# MCU_MKE185F512VLH16.net
KiCad netlist of a schematic drawn in Altium Designer
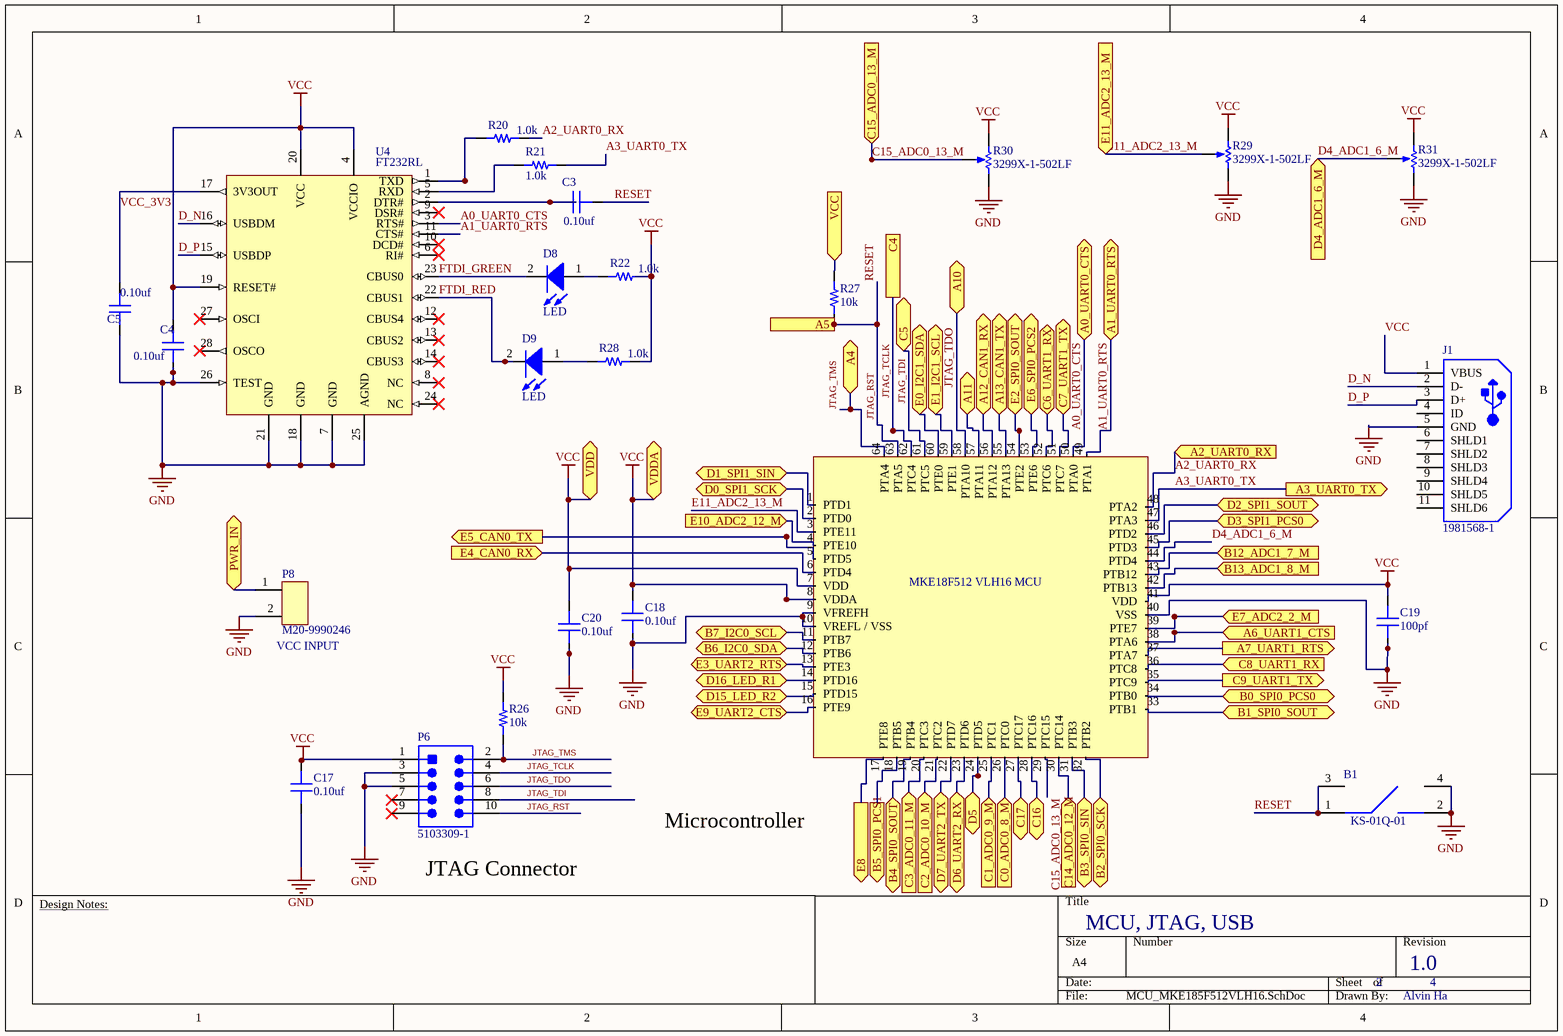
[diagram p0: MCU_MKE185F512VLH16.SchDoc]

(export (version "E")
  (design (tool "Eeschema 10.0.6"))
  (components
    (comp (ref "B1")
      (value "KS-01Q-01")
      (footprint "KS-01Q-01")
      (description "RESET button")
      (fields (field (name "CREATED_BY") "Austin") (field (name "UPDATED_BY") "Null"))
      (libsource (lib "Altium-Lib") (part "KS-01Q-01"))
    )
    (comp (ref "C3")
      (value "0.10uf")
      (footprint "CAP 0603/1608")
      (fields
        (field (name "Comment") "Capacitor MLCC 0.10uf 25V CAP 0603/1608")
        (field (name "CREATED_BY") "Nick Mah")
      )
      (libsource (lib "Altium-Lib") (part "Capacitor"))
    )
    (comp (ref "C4")
      (value "0.10uf")
      (footprint "CAP 0603/1608")
      (fields
        (field (name "Comment") "Capacitor MLCC 0.10uf 25V CAP 0603/1608")
        (field (name "CREATED_BY") "Nick Mah")
      )
      (libsource (lib "Altium-Lib") (part "Capacitor"))
    )
    (comp (ref "C5")
      (value "0.10uf")
      (footprint "CAP 0603/1608")
      (fields
        (field (name "Comment") "Capacitor MLCC 0.10uf 25V CAP 0603/1608")
        (field (name "CREATED_BY") "Nick Mah")
      )
      (libsource (lib "Altium-Lib") (part "Capacitor"))
    )
    (comp (ref "C17")
      (value "0.10uf")
      (footprint "CAP 0603/1608")
      (fields
        (field (name "Comment") "Capacitor MLCC 0.10uf 16V CAP 0603/1608")
        (field (name "CREATED_BY") "Nick Mah")
      )
      (libsource (lib "Altium-Lib") (part "Capacitor"))
    )
    (comp (ref "C18")
      (value "0.10uf")
      (footprint "CAP 0603/1608")
      (fields
        (field (name "Comment") "Capacitor MLCC 0.10uf 25V CAP 0603/1608")
        (field (name "CREATED_BY") "Nick Mah")
      )
      (libsource (lib "Altium-Lib") (part "Capacitor"))
    )
    (comp (ref "C19")
      (value "100pf")
      (footprint "CAP 0603/1608")
      (fields
        (field (name "Comment") "Capacitor MLCC 100pf 25V CAP 0603/1608")
        (field (name "CREATED_BY") "Nick Mah")
      )
      (libsource (lib "Altium-Lib") (part "Capacitor"))
    )
    (comp (ref "C20")
      (value "0.10uf")
      (footprint "CAP 0603/1608")
      (fields
        (field (name "Comment") "Capacitor MLCC 0.10uf 25V CAP 0603/1608")
        (field (name "CREATED_BY") "Nick Mah")
      )
      (libsource (lib "Altium-Lib") (part "Capacitor"))
    )
    (comp (ref "D8") (value "LED") (footprint "0805_LED") (libsource (lib "Altium-Lib") (part "LED")))
    (comp (ref "D9") (value "LED") (footprint "0805_LED") (libsource (lib "Altium-Lib") (part "LED")))
    (comp (ref "J1")
      (value "1981568-1")
      (footprint "TECO-1981568-5_V")
      (description "USB Micro Type B")
      (fields (field (name "CREATED_BY") "Aiku"))
      (libsource (lib "Altium-Lib") (part "USB-5-6SHLD"))
    )
    (comp (ref "P6")
      (value "5103309-1")
      (footprint "HDR2X5_SMT")
      (description "2 row connector")
      (fields (field (name "CREATED_BY") "Aiku"))
      (libsource (lib "Altium-Lib") (part "CN-2P-M-R10"))
    )
    (comp (ref "P8")
      (value "M20-9990246")
      (footprint "M20-9990246")
      (description "2 Pin VCC Power Header, Male")
      (fields (field (name "CREATED_BY") "Austin") (field (name "UPDATED_BY") "Null"))
      (libsource (lib "Altium-Lib") (part "M20-9990246"))
    )
    (comp (ref "R20")
      (value "1.0k")
      (footprint "RES 0805/2012")
      (fields
        (field (name "TOLERANCE") "1%")
        (field (name "POWER") "1/4W")
        (field (name "Comment") "Resistor 1.0k 0805 1/4W 1%")
        (field (name "CREATED_BY") "Nick Mah")
      )
      (libsource (lib "Altium-Lib") (part "Resistor"))
    )
    (comp (ref "R21")
      (value "1.0k")
      (footprint "RES 0805/2012")
      (fields
        (field (name "TOLERANCE") "1%")
        (field (name "POWER") "1/4W")
        (field (name "Comment") "Resistor 1.0k 0805 1/4W 1%")
        (field (name "CREATED_BY") "Nick Mah")
      )
      (libsource (lib "Altium-Lib") (part "Resistor"))
    )
    (comp (ref "R22")
      (value "1.0k")
      (footprint "RES 0805/2012")
      (fields
        (field (name "TOLERANCE") "1%")
        (field (name "POWER") "1/4W")
        (field (name "Comment") "Resistor 1.0k 0805 1/4W 1%")
        (field (name "CREATED_BY") "Nick Mah")
      )
      (libsource (lib "Altium-Lib") (part "Resistor"))
    )
    (comp (ref "R26")
      (value "10k")
      (footprint "RES 0603/1608")
      (fields
        (field (name "TOLERANCE") "1%")
        (field (name "POWER") "1/10W")
        (field (name "Comment") "Resistor 10k 0603 1/10W 1%")
        (field (name "CREATED_BY") "Nick Mah")
      )
      (libsource (lib "Altium-Lib") (part "Resistor"))
    )
    (comp (ref "R27")
      (value "10k")
      (footprint "RES 0603/1608")
      (fields
        (field (name "TOLERANCE") "5%")
        (field (name "POWER") "1/10W")
        (field (name "Comment") "Resistor 10k 0603 1/10W 5%")
        (field (name "CREATED_BY") "Nick Mah")
      )
      (libsource (lib "Altium-Lib") (part "Resistor"))
    )
    (comp (ref "R28")
      (value "1.0k")
      (footprint "RES 0805/2012")
      (fields
        (field (name "TOLERANCE") "1%")
        (field (name "POWER") "1/4W")
        (field (name "Comment") "Resistor 1.0k 0805 1/4W 1%")
        (field (name "CREATED_BY") "Nick Mah")
      )
      (libsource (lib "Altium-Lib") (part "Resistor"))
    )
    (comp (ref "R29")
      (value "3299X-1-502LF")
      (footprint "3299X-1-502LF")
      (libsource (lib "Altium-Lib") (part "3299X-1-502LF"))
    )
    (comp (ref "R30")
      (value "3299X-1-502LF")
      (footprint "3299X-1-502LF")
      (libsource (lib "Altium-Lib") (part "3299X-1-502LF"))
    )
    (comp (ref "R31")
      (value "3299X-1-502LF")
      (footprint "3299X-1-502LF")
      (libsource (lib "Altium-Lib") (part "3299X-1-502LF"))
    )
    (comp (ref "U3")
      (value "MKE18F512 VLH16 MCU")
      (footprint "TQFP64")
      (libsource (lib "Altium-Lib") (part "MKE18F512 VLH16 MCU"))
    )
    (comp (ref "U4")
      (value "FT232RL")
      (footprint "SSOP-28")
      (fields (field (name "CREATED_BY") "Kyle"))
      (libsource (lib "Altium-Lib") (part "FT232RL"))
    )
  )
  (nets
    (net (code "1") (name "/A0_UART0_CTS") (class "Default")
      (node (ref "U3") (pin "50") (pinfunction "PTA0_50") (pintype "input"))
      (node (ref "U4") (pin "3") (pinfunction "RTS#_3") (pintype "output"))
    )
    (net (code "2") (name "/A1_UART0_RTS") (class "Default")
      (node (ref "U3") (pin "49") (pinfunction "PTA1_49") (pintype "input"))
      (node (ref "U4") (pin "11") (pinfunction "CTS#_11") (pintype "input"))
    )
    (net (code "3") (name "/A2_UART0_RX") (class "Default")
      (node (ref "R20") (pin "2") (pinfunction "2_2") (pintype "passive"))
      (node (ref "U3") (pin "48") (pinfunction "PTA2_48") (pintype "input"))
    )
    (net (code "4") (name "/A3_UART0_TX") (class "Default")
      (node (ref "R21") (pin "2") (pinfunction "2_2") (pintype "passive"))
      (node (ref "U3") (pin "47") (pinfunction "PTA3_47") (pintype "input"))
    )
    (net (code "5") (name "/A6_UART1_CTS") (class "Default")
      (node (ref "U3") (pin "38") (pinfunction "PTA6_38") (pintype "input"))
    )
    (net (code "6") (name "/A7_UART1_RTS") (class "Default")
      (node (ref "U3") (pin "37") (pinfunction "PTA7_37") (pintype "input"))
    )
    (net (code "7") (name "/A11") (class "Default")
      (node (ref "U3") (pin "57") (pinfunction "PTA11_57") (pintype "input"))
    )
    (net (code "8") (name "/A12_CAN1_RX") (class "Default")
      (node (ref "U3") (pin "56") (pinfunction "PTA12_56") (pintype "input"))
    )
    (net (code "9") (name "/A13_CAN1_TX") (class "Default")
      (node (ref "U3") (pin "55") (pinfunction "PTA13_55") (pintype "input"))
    )
    (net (code "10") (name "/B0_SPI0_PCS0") (class "Default")
      (node (ref "U3") (pin "34") (pinfunction "PTB0_34") (pintype "input"))
    )
    (net (code "11") (name "/B1_SPI0_SOUT") (class "Default")
      (node (ref "U3") (pin "33") (pinfunction "PTB1_33") (pintype "input"))
    )
    (net (code "12") (name "/B2_SPI0_SCK") (class "Default")
      (node (ref "U3") (pin "32") (pinfunction "PTB2_32") (pintype "input"))
    )
    (net (code "13") (name "/B3_SPI0_SIN") (class "Default")
      (node (ref "U3") (pin "31") (pinfunction "PTB3_31") (pintype "input"))
    )
    (net (code "14") (name "/B4_SPI0_SOUT") (class "Default")
      (node (ref "U3") (pin "19") (pinfunction "PTB4_19") (pintype "input"))
    )
    (net (code "15") (name "/B5_SPI0_PCS1") (class "Default")
      (node (ref "U3") (pin "18") (pinfunction "PTB5_18") (pintype "input"))
    )
    (net (code "16") (name "/B6_I2C0_SDA") (class "Default")
      (node (ref "U3") (pin "12") (pinfunction "PTB6_12") (pintype "input"))
    )
    (net (code "17") (name "/B7_I2C0_SCL") (class "Default")
      (node (ref "U3") (pin "11") (pinfunction "PTB7_11") (pintype "input"))
    )
    (net (code "18") (name "/B12_ADC1_7_M") (class "Default")
      (node (ref "U3") (pin "43") (pinfunction "PTB12_43") (pintype "input"))
    )
    (net (code "19") (name "/B13_ADC1_8_M") (class "Default")
      (node (ref "U3") (pin "42") (pinfunction "PTB13_42") (pintype "input"))
    )
    (net (code "20") (name "/C0_ADC0_8_M") (class "Default")
      (node (ref "U3") (pin "26") (pinfunction "PTC0_26") (pintype "input"))
    )
    (net (code "21") (name "/C1_ADC0_9_M") (class "Default")
      (node (ref "U3") (pin "25") (pinfunction "PTC1_25") (pintype "input"))
    )
    (net (code "22") (name "/C2_ADC0_10_M") (class "Default")
      (node (ref "U3") (pin "21") (pinfunction "PTC2_21") (pintype "input"))
    )
    (net (code "23") (name "/C3_ADC0_11_M") (class "Default")
      (node (ref "U3") (pin "20") (pinfunction "PTC3_20") (pintype "input"))
    )
    (net (code "24") (name "/C6_UART1_RX") (class "Default")
      (node (ref "U3") (pin "52") (pinfunction "PTC6_52") (pintype "input"))
    )
    (net (code "25") (name "/C7_UART1_TX") (class "Default")
      (node (ref "U3") (pin "51") (pinfunction "PTC7_51") (pintype "input"))
    )
    (net (code "26") (name "/C8_UART1_RX") (class "Default")
      (node (ref "U3") (pin "36") (pinfunction "PTC8_36") (pintype "input"))
    )
    (net (code "27") (name "/C9_UART1_TX") (class "Default")
      (node (ref "U3") (pin "35") (pinfunction "PTC9_35") (pintype "input"))
    )
    (net (code "28") (name "/C14_ADC0_12_M") (class "Default")
      (node (ref "U3") (pin "30") (pinfunction "PTC14_30") (pintype "input"))
    )
    (net (code "29") (name "/C15_ADC0_13_M") (class "Default")
      (node (ref "R30") (pin "2") (pinfunction "TAP_2") (pintype "passive"))
      (node (ref "U3") (pin "29") (pinfunction "PTC15_29") (pintype "input"))
    )
    (net (code "30") (name "/C16") (class "Default")
      (node (ref "U3") (pin "28") (pinfunction "PTC16_28") (pintype "input"))
    )
    (net (code "31") (name "/C17") (class "Default")
      (node (ref "U3") (pin "27") (pinfunction "PTC17_27") (pintype "input"))
    )
    (net (code "32") (name "/D0_SPI1_SCK") (class "Default")
      (node (ref "U3") (pin "2") (pinfunction "PTD0_2") (pintype "input"))
    )
    (net (code "33") (name "/D1_SPI1_SIN") (class "Default")
      (node (ref "U3") (pin "1") (pinfunction "PTD1_1") (pintype "input"))
    )
    (net (code "34") (name "/D2_SPI1_SOUT") (class "Default")
      (node (ref "U3") (pin "46") (pinfunction "PTD2_46") (pintype "input"))
    )
    (net (code "35") (name "/D3_SPI1_PCS0") (class "Default")
      (node (ref "U3") (pin "45") (pinfunction "PTD3_45") (pintype "input"))
    )
    (net (code "36") (name "/D4_ADC1_6_M") (class "Default")
      (node (ref "R31") (pin "2") (pinfunction "TAP_2") (pintype "passive"))
      (node (ref "U3") (pin "44") (pinfunction "PTD4_44") (pintype "input"))
    )
    (net (code "37") (name "/D5") (class "Default")
      (node (ref "U3") (pin "24") (pinfunction "PTD5_24") (pintype "input"))
    )
    (net (code "38") (name "/D6_UART2_RX") (class "Default")
      (node (ref "U3") (pin "23") (pinfunction "PTD6_23") (pintype "input"))
    )
    (net (code "39") (name "/D7_UART2_TX") (class "Default")
      (node (ref "U3") (pin "22") (pinfunction "PTD7_22") (pintype "input"))
    )
    (net (code "40") (name "/D15_LED_R2") (class "Default")
      (node (ref "U3") (pin "15") (pinfunction "PTD15_15") (pintype "input"))
    )
    (net (code "41") (name "/D16_LED_R1") (class "Default")
      (node (ref "U3") (pin "14") (pinfunction "PTD16_14") (pintype "input"))
    )
    (net (code "42") (name "/D_N") (class "Default")
      (node (ref "J1") (pin "2") (pinfunction "D-_2") (pintype "passive"))
      (node (ref "U4") (pin "16") (pinfunction "USBDM_16") (pintype "bidirectional"))
    )
    (net (code "43") (name "/D_P") (class "Default")
      (node (ref "J1") (pin "3") (pinfunction "D+_3") (pintype "passive"))
      (node (ref "U4") (pin "15") (pinfunction "USBDP_15") (pintype "bidirectional"))
    )
    (net (code "44") (name "/E0_I2C1_SDA") (class "Default")
      (node (ref "U3") (pin "60") (pinfunction "PTE0_60") (pintype "input"))
    )
    (net (code "45") (name "/E1_I2C1_SCL") (class "Default")
      (node (ref "U3") (pin "59") (pinfunction "PTE1_59") (pintype "input"))
    )
    (net (code "46") (name "/E2_SPI0_SOUT") (class "Default")
      (node (ref "U3") (pin "54") (pinfunction "PTE2_54") (pintype "input"))
    )
    (net (code "47") (name "/E3_UART2_RTS") (class "Default")
      (node (ref "U3") (pin "13") (pinfunction "PTE3_13") (pintype "input"))
    )
    (net (code "48") (name "/E4_CAN0_RX") (class "Default")
      (node (ref "U3") (pin "6") (pinfunction "PTD4_6") (pintype "input"))
    )
    (net (code "49") (name "/E5_CAN0_TX") (class "Default")
      (node (ref "U3") (pin "5") (pinfunction "PTD5_5") (pintype "input"))
    )
    (net (code "50") (name "/E6_SPI0_PCS2") (class "Default")
      (node (ref "U3") (pin "53") (pinfunction "PTE6_53") (pintype "input"))
    )
    (net (code "51") (name "/E7_ADC2_2_M") (class "Default")
      (node (ref "U3") (pin "39") (pinfunction "PTE7_39") (pintype "input"))
    )
    (net (code "52") (name "/E8") (class "Default")
      (node (ref "U3") (pin "17") (pinfunction "PTE8_17") (pintype "input"))
    )
    (net (code "53") (name "/E9_UART2_CTS") (class "Default")
      (node (ref "U3") (pin "16") (pinfunction "PTE9_16") (pintype "input"))
    )
    (net (code "54") (name "/E10_ADC2_12_M") (class "Default")
      (node (ref "U3") (pin "4") (pinfunction "PTE10_4") (pintype "input"))
    )
    (net (code "55") (name "/E11_ADC2_13_M") (class "Default")
      (node (ref "R29") (pin "2") (pinfunction "TAP_2") (pintype "passive"))
      (node (ref "U3") (pin "3") (pinfunction "PTE11_3") (pintype "input"))
    )
    (net (code "56") (name "/FTDI_GREEN") (class "Default")
      (node (ref "D8") (pin "2") (pinfunction "K_2") (pintype "passive"))
      (node (ref "U4") (pin "23") (pinfunction "CBUS0_23") (pintype "bidirectional"))
    )
    (net (code "57") (name "/FTDI_RED") (class "Default")
      (node (ref "D9") (pin "2") (pinfunction "K_2") (pintype "passive"))
      (node (ref "U4") (pin "22") (pinfunction "CBUS1_22") (pintype "bidirectional"))
    )
    (net (code "58") (name "/JTAG_RST") (class "Default")
      (node (ref "B1") (pin "1") (pinfunction "1_1") (pintype "passive"))
      (node (ref "B1") (pin "3") (pinfunction "3_3") (pintype "passive"))
      (node (ref "C3") (pin "2") (pinfunction "2_2") (pintype "passive"))
      (node (ref "P6") (pin "10") (pinfunction "10_10") (pintype "passive"))
      (node (ref "R27") (pin "1") (pinfunction "1_1") (pintype "passive"))
      (node (ref "U3") (pin "63") (pinfunction "PTA5_63") (pintype "input"))
    )
    (net (code "59") (name "/JTAG_TCLK") (class "Default")
      (node (ref "P6") (pin "4") (pinfunction "4_4") (pintype "passive"))
      (node (ref "U3") (pin "62") (pinfunction "PTC4_62") (pintype "input"))
    )
    (net (code "60") (name "/JTAG_TDI") (class "Default")
      (node (ref "P6") (pin "8") (pinfunction "8_8") (pintype "passive"))
      (node (ref "U3") (pin "61") (pinfunction "PTC5_61") (pintype "input"))
    )
    (net (code "61") (name "/JTAG_TDO") (class "Default")
      (node (ref "P6") (pin "6") (pinfunction "6_6") (pintype "passive"))
      (node (ref "U3") (pin "58") (pinfunction "PTA10_58") (pintype "input"))
    )
    (net (code "62") (name "/JTAG_TMS") (class "Default")
      (node (ref "P6") (pin "2") (pinfunction "2_2") (pintype "passive"))
      (node (ref "R26") (pin "1") (pinfunction "1_1") (pintype "passive"))
      (node (ref "U3") (pin "64") (pinfunction "PTA4_64") (pintype "input"))
    )
    (net (code "63") (name "/PWR_IN") (class "Default")
      (node (ref "P8") (pin "1") (pinfunction "1_1") (pintype "passive"))
    )
    (net (code "64") (name "/VCC_3V3") (class "Default")
      (node (ref "C5") (pin "2") (pinfunction "2_2") (pintype "passive"))
      (node (ref "U4") (pin "17") (pinfunction "3V3OUT_17") (pintype "output"))
    )
    (net (code "65") (name "GND") (class "Default")
      (node (ref "B1") (pin "2") (pinfunction "2_2") (pintype "passive"))
      (node (ref "B1") (pin "4") (pinfunction "4_4") (pintype "passive"))
      (node (ref "C17") (pin "1") (pinfunction "1_1") (pintype "passive"))
      (node (ref "C18") (pin "1") (pinfunction "1_1") (pintype "passive"))
      (node (ref "C19") (pin "1") (pinfunction "1_1") (pintype "passive"))
      (node (ref "C20") (pin "1") (pinfunction "1_1") (pintype "passive"))
      (node (ref "C4") (pin "1") (pinfunction "1_1") (pintype "passive"))
      (node (ref "C5") (pin "1") (pinfunction "1_1") (pintype "passive"))
      (node (ref "J1") (pin "5") (pinfunction "GND_5") (pintype "passive"))
      (node (ref "P6") (pin "3") (pinfunction "3_3") (pintype "passive"))
      (node (ref "P6") (pin "5") (pinfunction "5_5") (pintype "passive"))
      (node (ref "R29") (pin "3") (pinfunction "BOT_3") (pintype "passive"))
      (node (ref "R30") (pin "3") (pinfunction "BOT_3") (pintype "passive"))
      (node (ref "R31") (pin "3") (pinfunction "BOT_3") (pintype "passive"))
      (node (ref "U3") (pin "10") (pinfunction "VREFL_/_VSS_10") (pintype "input"))
      (node (ref "U3") (pin "40") (pinfunction "VSS_40") (pintype "input"))
      (node (ref "U3") (pin "9") (pinfunction "VFREFH_9") (pintype "input"))
      (node (ref "U4") (pin "18") (pinfunction "GND_18") (pintype "passive"))
      (node (ref "U4") (pin "21") (pinfunction "GND_21") (pintype "passive"))
      (node (ref "U4") (pin "25") (pinfunction "AGND_25") (pintype "passive"))
      (node (ref "U4") (pin "26") (pinfunction "TEST_26") (pintype "input"))
      (node (ref "U4") (pin "7") (pinfunction "GND_7") (pintype "passive"))
    )
    (net (code "66") (name "Net-(D8-A)") (class "Default")
      (node (ref "D8") (pin "1") (pinfunction "A_1") (pintype "passive"))
      (node (ref "R22") (pin "1") (pinfunction "1_1") (pintype "passive"))
    )
    (net (code "67") (name "Net-(D9-A)") (class "Default")
      (node (ref "D9") (pin "1") (pinfunction "A_1") (pintype "passive"))
      (node (ref "R28") (pin "1") (pinfunction "1_1") (pintype "passive"))
    )
    (net (code "68") (name "Net-(U4-DTR#)") (class "Default")
      (node (ref "C3") (pin "1") (pinfunction "1_1") (pintype "passive"))
      (node (ref "U4") (pin "2") (pinfunction "DTR#_2") (pintype "output"))
    )
    (net (code "69") (name "Net-(U4-RXD)") (class "Default")
      (node (ref "R21") (pin "1") (pinfunction "1_1") (pintype "passive"))
      (node (ref "U4") (pin "5") (pinfunction "RXD_5") (pintype "input"))
    )
    (net (code "70") (name "Net-(U4-TXD)") (class "Default")
      (node (ref "R20") (pin "1") (pinfunction "1_1") (pintype "passive"))
      (node (ref "U4") (pin "1") (pinfunction "TXD_1") (pintype "output"))
    )
    (net (code "71") (name "VCC") (class "Default")
      (node (ref "C17") (pin "2") (pinfunction "2_2") (pintype "passive"))
      (node (ref "C18") (pin "2") (pinfunction "2_2") (pintype "passive"))
      (node (ref "C19") (pin "2") (pinfunction "2_2") (pintype "passive"))
      (node (ref "C20") (pin "2") (pinfunction "2_2") (pintype "passive"))
      (node (ref "C4") (pin "2") (pinfunction "2_2") (pintype "passive"))
      (node (ref "J1") (pin "1") (pinfunction "VBUS_1") (pintype "passive"))
      (node (ref "P6") (pin "1") (pinfunction "1_1") (pintype "passive"))
      (node (ref "R22") (pin "2") (pinfunction "2_2") (pintype "passive"))
      (node (ref "R26") (pin "2") (pinfunction "2_2") (pintype "passive"))
      (node (ref "R27") (pin "2") (pinfunction "2_2") (pintype "passive"))
      (node (ref "R28") (pin "2") (pinfunction "2_2") (pintype "passive"))
      (node (ref "R29") (pin "1") (pinfunction "TOP_1") (pintype "passive"))
      (node (ref "R30") (pin "1") (pinfunction "TOP_1") (pintype "passive"))
      (node (ref "R31") (pin "1") (pinfunction "TOP_1") (pintype "passive"))
      (node (ref "U3") (pin "41") (pinfunction "VDD_41") (pintype "input"))
      (node (ref "U3") (pin "7") (pinfunction "VDD_7") (pintype "input"))
      (node (ref "U3") (pin "8") (pinfunction "VDDA_8") (pintype "input"))
      (node (ref "U4") (pin "19") (pinfunction "RESET#_19") (pintype "input"))
      (node (ref "U4") (pin "20") (pinfunction "VCC_20") (pintype "passive"))
      (node (ref "U4") (pin "4") (pinfunction "VCCIO_4") (pintype "passive"))
    )
    (net (code "72") (name "unconnected-(J1-ID-Pad4)") (class "Default")
      (node (ref "J1") (pin "4") (pinfunction "ID_4") (pintype "passive"))
    )
    (net (code "73") (name "unconnected-(J1-SHLD1-Pad6)") (class "Default")
      (node (ref "J1") (pin "6") (pinfunction "SHLD1_6") (pintype "passive"))
    )
    (net (code "74") (name "unconnected-(J1-SHLD2-Pad7)") (class "Default")
      (node (ref "J1") (pin "7") (pinfunction "SHLD2_7") (pintype "passive"))
    )
    (net (code "75") (name "unconnected-(J1-SHLD3-Pad8)") (class "Default")
      (node (ref "J1") (pin "8") (pinfunction "SHLD3_8") (pintype "passive"))
    )
    (net (code "76") (name "unconnected-(J1-SHLD4-Pad9)") (class "Default")
      (node (ref "J1") (pin "9") (pinfunction "SHLD4_9") (pintype "passive"))
    )
    (net (code "77") (name "unconnected-(J1-SHLD5-Pad10)") (class "Default")
      (node (ref "J1") (pin "10") (pinfunction "SHLD5_10") (pintype "passive"))
    )
    (net (code "78") (name "unconnected-(J1-SHLD6-Pad11)") (class "Default")
      (node (ref "J1") (pin "11") (pinfunction "SHLD6_11") (pintype "passive"))
    )
    (net (code "79") (name "unconnected-(P6-Pad7)") (class "Default")
      (node (ref "P6") (pin "7") (pinfunction "7_7") (pintype "passive+no_connect"))
    )
    (net (code "80") (name "unconnected-(P6-Pad9)") (class "Default")
      (node (ref "P6") (pin "9") (pinfunction "9_9") (pintype "passive+no_connect"))
    )
    (net (code "81") (name "unconnected-(P8-Pad2)") (class "Default")
      (node (ref "P8") (pin "2") (pinfunction "2_2") (pintype "passive"))
    )
    (net (code "82") (name "unconnected-(U4-CBUS2-Pad13)") (class "Default")
      (node (ref "U4") (pin "13") (pinfunction "CBUS2_13") (pintype "bidirectional+no_connect"))
    )
    (net (code "83") (name "unconnected-(U4-CBUS3-Pad14)") (class "Default")
      (node (ref "U4") (pin "14") (pinfunction "CBUS3_14") (pintype "bidirectional+no_connect"))
    )
    (net (code "84") (name "unconnected-(U4-CBUS4-Pad12)") (class "Default")
      (node (ref "U4") (pin "12") (pinfunction "CBUS4_12") (pintype "bidirectional+no_connect"))
    )
    (net (code "85") (name "unconnected-(U4-DCD#-Pad10)") (class "Default")
      (node (ref "U4") (pin "10") (pinfunction "DCD#_10") (pintype "input+no_connect"))
    )
    (net (code "86") (name "unconnected-(U4-DSR#-Pad9)") (class "Default")
      (node (ref "U4") (pin "9") (pinfunction "DSR#_9") (pintype "input+no_connect"))
    )
    (net (code "87") (name "unconnected-(U4-NC-Pad8)") (class "Default")
      (node (ref "U4") (pin "8") (pinfunction "NC_8") (pintype "input+no_connect"))
    )
    (net (code "88") (name "unconnected-(U4-NC-Pad24)") (class "Default")
      (node (ref "U4") (pin "24") (pinfunction "NC_24") (pintype "input+no_connect"))
    )
    (net (code "89") (name "unconnected-(U4-OSCI-Pad27)") (class "Default")
      (node (ref "U4") (pin "27") (pinfunction "OSCI_27") (pintype "input+no_connect"))
    )
    (net (code "90") (name "unconnected-(U4-OSCO-Pad28)") (class "Default")
      (node (ref "U4") (pin "28") (pinfunction "OSCO_28") (pintype "output+no_connect"))
    )
    (net (code "91") (name "unconnected-(U4-RI#-Pad6)") (class "Default")
      (node (ref "U4") (pin "6") (pinfunction "RI#_6") (pintype "input+no_connect"))
    )
  )
)
